# F3-Quad-Brushed-SIDE-USB.net
KiCad netlist of a schematic drawn in EAGLE
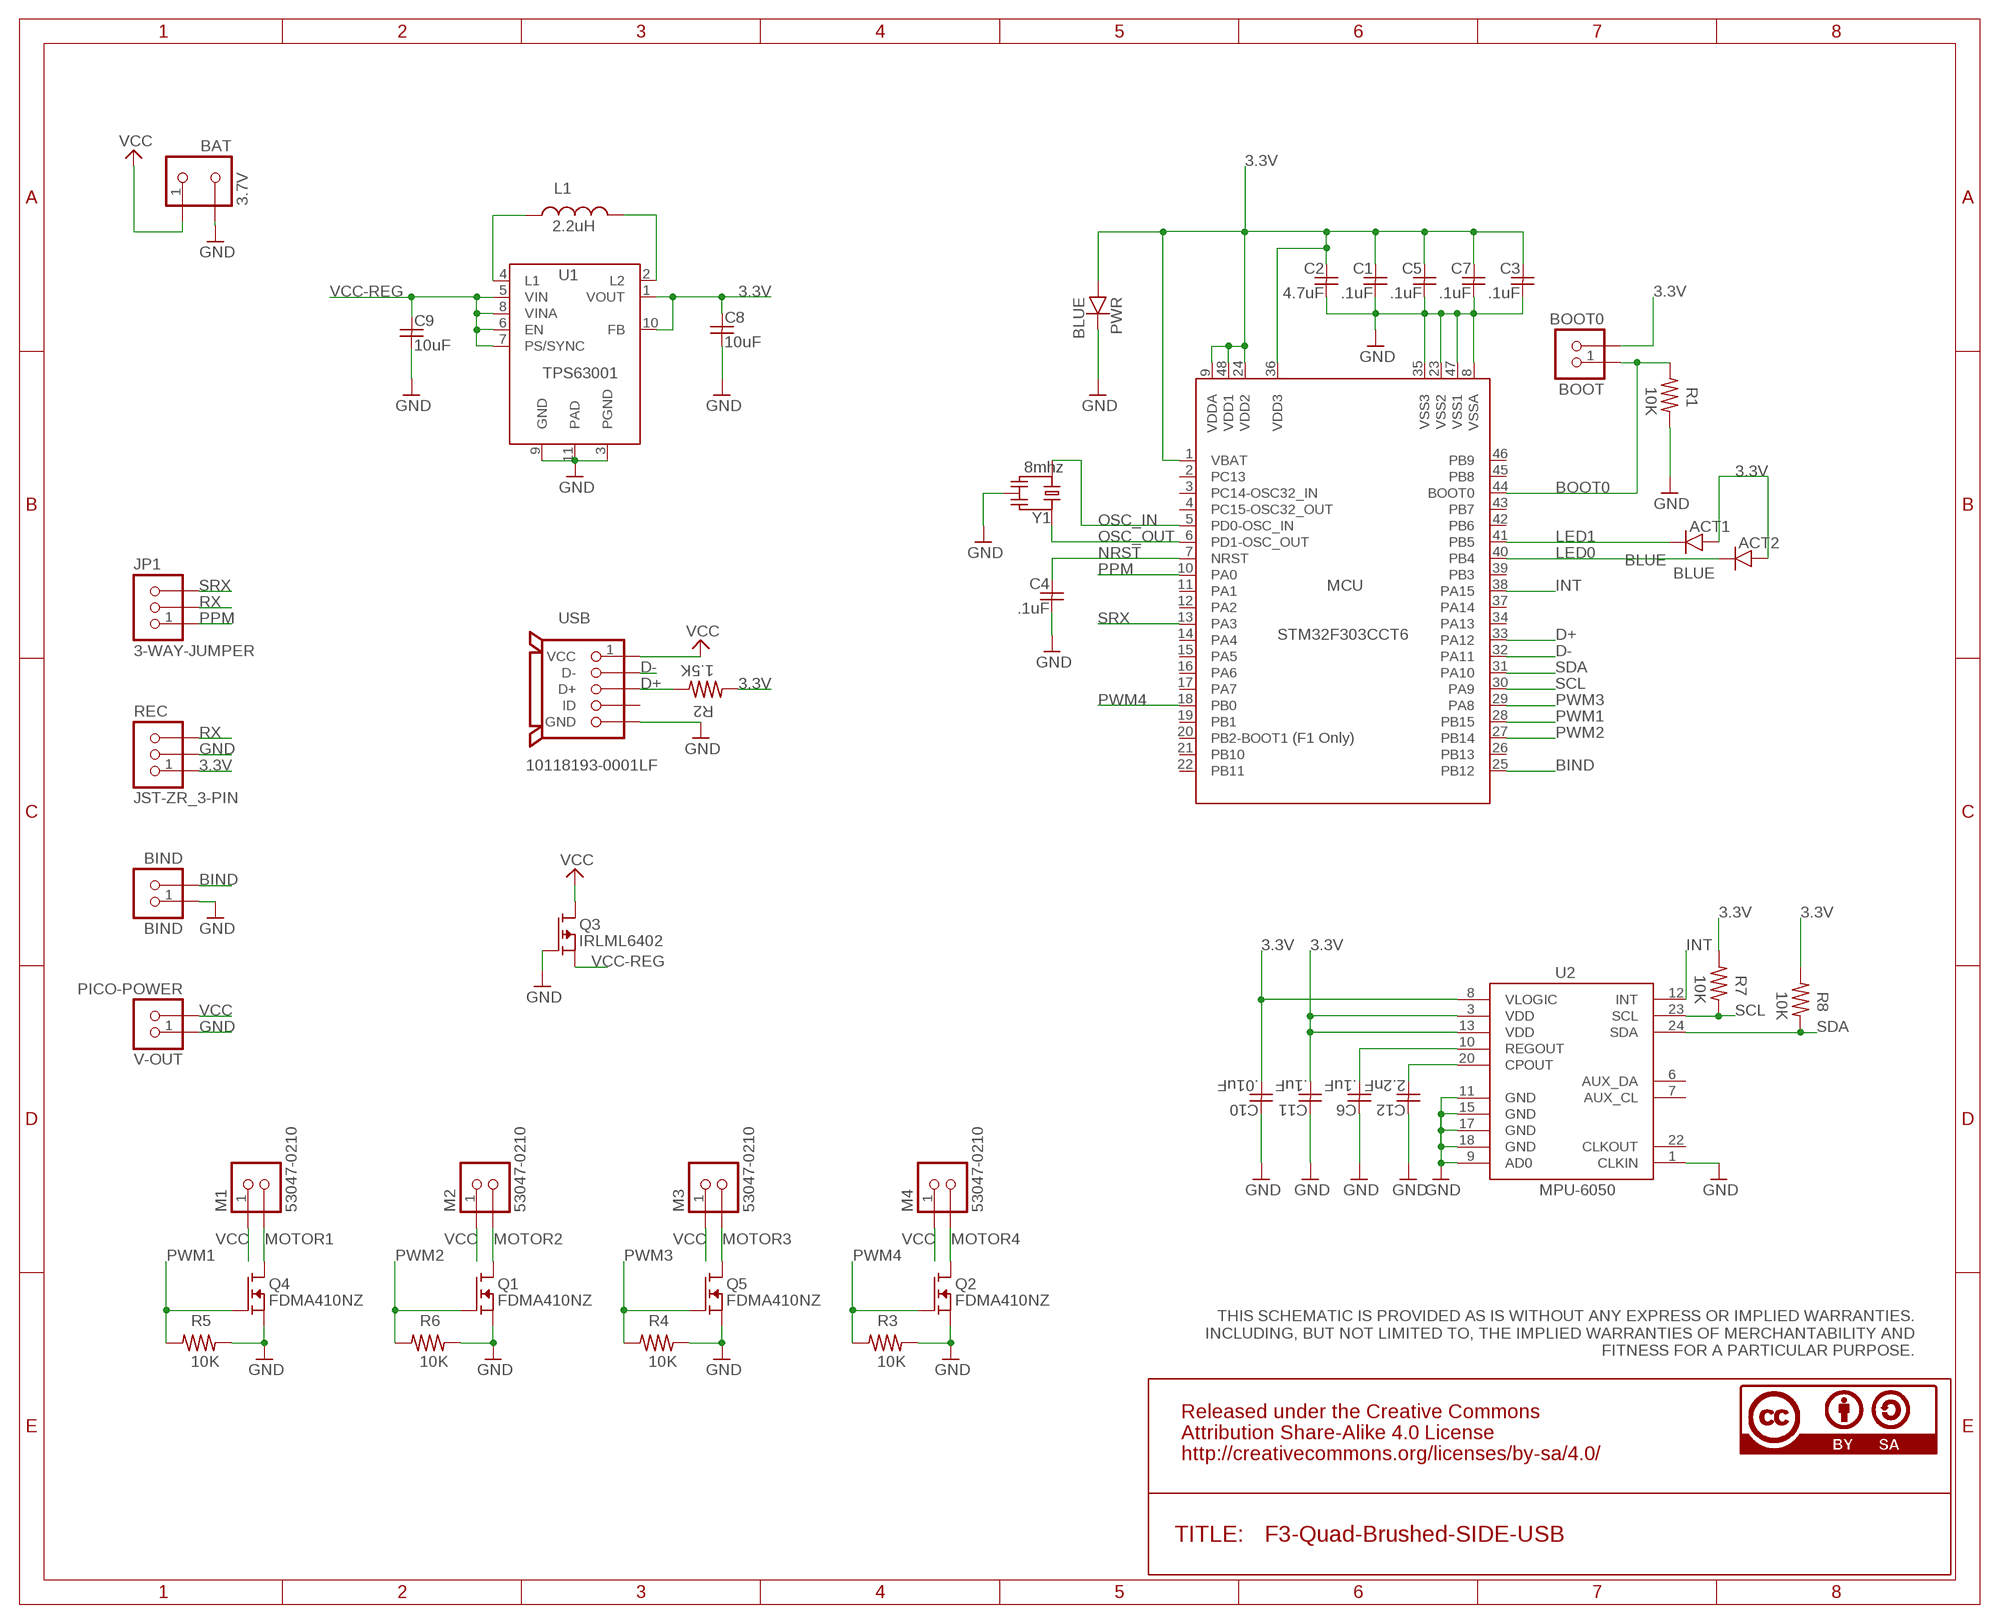
[diagram p0: schematic, sheet 1]

(export (version "E")
  (design (tool "Eeschema 10.0.6"))
  (components
    (comp (ref "ACT1")
      (value "BLUE")
      (footprint "eagle-import:SMD-CHIP-LED-0805")
      (fields (field (name "MF") "Kingbright") (field (name "MPN") "APHCM2012QBC/D-F01"))
      (libsource (lib "eagle-import") (part "SMD-CHIP-LED-0805"))
    )
    (comp (ref "ACT2")
      (value "BLUE")
      (footprint "eagle-import:SMD-CHIP-LED-0805")
      (fields (field (name "MF") "Kingbright") (field (name "MPN") "APHCM2012QBC/D-F01"))
      (libsource (lib "eagle-import") (part "SMD-CHIP-LED-0805"))
    )
    (comp (ref "BAT")
      (value "3.7V")
      (footprint "eagle-import:S2B-PH-K-S")
      (fields (field (name "MF") "JST") (field (name "MPN") "S2B-PH-K-S"))
      (libsource (lib "eagle-import") (part "JST-PH-BAT"))
    )
    (comp (ref "BIND")
      (value "BIND")
      (footprint "eagle-import:B3U-1000P(M)")
      (fields (field (name "MF") "Omron") (field (name "MPN") "B3U-1000P"))
      (libsource (lib "eagle-import") (part "TACTILE-SWITCH"))
    )
    (comp (ref "BOOT")
      (value "BOOT0")
      (footprint "eagle-import:B3U-1000P(M)")
      (fields (field (name "MF") "Omron") (field (name "MPN") "B3U-1000P"))
      (libsource (lib "eagle-import") (part "TACTILE-SWITCH"))
    )
    (comp (ref "C1")
      (value ".1uF")
      (footprint "eagle-import:MUR-CAP-0603")
      (fields (field (name "MF") "Murata") (field (name "MPN") "GRM188R71C104KA01D"))
      (libsource (lib "eagle-import") (part "CAPACITOR.1UF"))
    )
    (comp (ref "C2")
      (value "4.7uF")
      (footprint "eagle-import:MUR-CAP-0603")
      (fields (field (name "MF") "Murata") (field (name "MPN") "GRJ188C70J475KE11D"))
      (libsource (lib "eagle-import") (part "CAPACITOR4.7UF"))
    )
    (comp (ref "C3")
      (value ".1uF")
      (footprint "eagle-import:MUR-CAP-0603")
      (fields (field (name "MF") "Murata") (field (name "MPN") "GRM188R71C104KA01D"))
      (libsource (lib "eagle-import") (part "CAPACITOR.1UF"))
    )
    (comp (ref "C4")
      (value ".1uF")
      (footprint "eagle-import:MUR-CAP-0603")
      (fields (field (name "MF") "Murata") (field (name "MPN") "GRM188R71C104KA01D"))
      (libsource (lib "eagle-import") (part "CAPACITOR.1UF"))
    )
    (comp (ref "C5")
      (value ".1uF")
      (footprint "eagle-import:MUR-CAP-0603")
      (fields (field (name "MF") "Murata") (field (name "MPN") "GRM188R71C104KA01D"))
      (libsource (lib "eagle-import") (part "CAPACITOR.1UF"))
    )
    (comp (ref "C6")
      (value ".1uF")
      (footprint "eagle-import:MUR-CAP-0603")
      (fields (field (name "MF") "Murata") (field (name "MPN") "GRM188R71C104KA01D"))
      (libsource (lib "eagle-import") (part "CAPACITOR.1UF"))
    )
    (comp (ref "C7")
      (value ".1uF")
      (footprint "eagle-import:MUR-CAP-0603")
      (fields (field (name "MF") "Murata") (field (name "MPN") "GRM188R71C104KA01D"))
      (libsource (lib "eagle-import") (part "CAPACITOR.1UF"))
    )
    (comp (ref "C8")
      (value "10uF")
      (footprint "eagle-import:YUDEN-CAP-0805")
      (fields (field (name "MF") "Taiyo Yuden") (field (name "MPN") "JMK212AB7106KG-T"))
      (libsource (lib "eagle-import") (part "CAPACITOR10UF"))
    )
    (comp (ref "C9")
      (value "10uF")
      (footprint "eagle-import:YUDEN-CAP-0805")
      (fields (field (name "MF") "Taiyo Yuden") (field (name "MPN") "JMK212AB7106KG-T"))
      (libsource (lib "eagle-import") (part "CAPACITOR10UF"))
    )
    (comp (ref "C10")
      (value ".01uF")
      (footprint "eagle-import:MUR-CAP-0603")
      (fields (field (name "MF") "Murata") (field (name "MPN") "GRM188R71C103KA01D"))
      (libsource (lib "eagle-import") (part "CAPACITOR.01UF"))
    )
    (comp (ref "C11")
      (value ".1uF")
      (footprint "eagle-import:MUR-CAP-0603")
      (fields (field (name "MF") "Murata") (field (name "MPN") "GRM188R71C104KA01D"))
      (libsource (lib "eagle-import") (part "CAPACITOR.1UF"))
    )
    (comp (ref "C12")
      (value "2.2nF")
      (footprint "eagle-import:MUR-CAP-0603")
      (fields (field (name "MF") "Murata") (field (name "MPN") "GRM188R71C222KA01D"))
      (libsource (lib "eagle-import") (part "CAPACITOR2.2NF"))
    )
    (comp (ref "JP1")
      (value "3-WAY-JUMPER")
      (footprint "eagle-import:3-WAY-JUMPER")
      (libsource (lib "eagle-import") (part "3-WAY-JUMPER"))
    )
    (comp (ref "L1")
      (value "2.2uH")
      (footprint "eagle-import:NR301X")
      (fields (field (name "MF") "Taiyo Yuden") (field (name "MPN") "NR3015T2R2M"))
      (libsource (lib "eagle-import") (part "NR301X"))
    )
    (comp (ref "M1")
      (value "53047-0210")
      (footprint "eagle-import:PICO-53047-02")
      (fields (field (name "MF") "MOLEX"))
      (libsource (lib "eagle-import") (part "PICO-1.25-MOTOR"))
    )
    (comp (ref "M2")
      (value "53047-0210")
      (footprint "eagle-import:PICO-53047-02")
      (fields (field (name "MF") "MOLEX"))
      (libsource (lib "eagle-import") (part "PICO-1.25-MOTOR"))
    )
    (comp (ref "M3")
      (value "53047-0210")
      (footprint "eagle-import:PICO-53047-02")
      (fields (field (name "MF") "MOLEX"))
      (libsource (lib "eagle-import") (part "PICO-1.25-MOTOR"))
    )
    (comp (ref "M4")
      (value "53047-0210")
      (footprint "eagle-import:PICO-53047-02")
      (fields (field (name "MF") "MOLEX"))
      (libsource (lib "eagle-import") (part "PICO-1.25-MOTOR"))
    )
    (comp (ref "MCU")
      (value "STM32F303CCT6")
      (footprint "eagle-import:LQFP48-7X7")
      (fields (field (name "MF") "ST"))
      (libsource (lib "eagle-import") (part "STM32FX03-F3"))
    )
    (comp (ref "PWR")
      (value "BLUE")
      (footprint "eagle-import:SMD-CHIP-LED-0805")
      (fields (field (name "MF") "Kingbright") (field (name "MPN") "APHCM2012QBC/D-F01"))
      (libsource (lib "eagle-import") (part "SMD-CHIP-LED-0805"))
    )
    (comp (ref "Q1")
      (value "FDMA410NZ")
      (footprint "eagle-import:MICROFET-2X2")
      (fields (field (name "MF") "Fairchild"))
      (libsource (lib "eagle-import") (part "FDMA410NZ"))
    )
    (comp (ref "Q2")
      (value "FDMA410NZ")
      (footprint "eagle-import:MICROFET-2X2")
      (fields (field (name "MF") "Fairchild"))
      (libsource (lib "eagle-import") (part "FDMA410NZ"))
    )
    (comp (ref "Q3")
      (value "IRLML6402")
      (footprint "eagle-import:SOT-23")
      (fields (field (name "MF") "IR"))
      (libsource (lib "eagle-import") (part "MOSFET-P"))
    )
    (comp (ref "Q4")
      (value "FDMA410NZ")
      (footprint "eagle-import:MICROFET-2X2")
      (fields (field (name "MF") "Fairchild"))
      (libsource (lib "eagle-import") (part "FDMA410NZ"))
    )
    (comp (ref "Q5")
      (value "FDMA410NZ")
      (footprint "eagle-import:MICROFET-2X2")
      (fields (field (name "MF") "Fairchild"))
      (libsource (lib "eagle-import") (part "FDMA410NZ"))
    )
    (comp (ref "R1")
      (value "10K")
      (footprint "eagle-import:VISH-RES-0603")
      (fields (field (name "MF") "Vishay") (field (name "MPN") "CRCW060310K0FKEAHP"))
      (libsource (lib "eagle-import") (part "RESISTOR10K"))
    )
    (comp (ref "R2")
      (value "1.5K")
      (footprint "eagle-import:VISH-RES-0603")
      (fields (field (name "MF") "Vishay") (field (name "MPN") "CRCW06031K50FKEAHP"))
      (libsource (lib "eagle-import") (part "RESISTOR1.5K"))
    )
    (comp (ref "R3")
      (value "10K")
      (footprint "eagle-import:VISH-RES-0603")
      (fields (field (name "MF") "Vishay") (field (name "MPN") "CRCW060310K0FKEAHP"))
      (libsource (lib "eagle-import") (part "RESISTOR10K"))
    )
    (comp (ref "R4")
      (value "10K")
      (footprint "eagle-import:VISH-RES-0603")
      (fields (field (name "MF") "Vishay") (field (name "MPN") "CRCW060310K0FKEAHP"))
      (libsource (lib "eagle-import") (part "RESISTOR10K"))
    )
    (comp (ref "R5")
      (value "10K")
      (footprint "eagle-import:VISH-RES-0603")
      (fields (field (name "MF") "Vishay") (field (name "MPN") "CRCW060310K0FKEAHP"))
      (libsource (lib "eagle-import") (part "RESISTOR10K"))
    )
    (comp (ref "R6")
      (value "10K")
      (footprint "eagle-import:VISH-RES-0603")
      (fields (field (name "MF") "Vishay") (field (name "MPN") "CRCW060310K0FKEAHP"))
      (libsource (lib "eagle-import") (part "RESISTOR10K"))
    )
    (comp (ref "R7")
      (value "10K")
      (footprint "eagle-import:VISH-RES-0603")
      (fields (field (name "MF") "Vishay") (field (name "MPN") "CRCW060310K0FKEAHP"))
      (libsource (lib "eagle-import") (part "RESISTOR10K"))
    )
    (comp (ref "R8")
      (value "10K")
      (footprint "eagle-import:VISH-RES-0603")
      (fields (field (name "MF") "Vishay") (field (name "MPN") "CRCW060310K0FKEAHP"))
      (libsource (lib "eagle-import") (part "RESISTOR10K"))
    )
    (comp (ref "REC")
      (value "JST-ZR_3-PIN")
      (footprint "eagle-import:S3B-ZR")
      (fields (field (name "MF") "JST") (field (name "MPN") "S3B-ZR"))
      (libsource (lib "eagle-import") (part "JST-ZR_3-PIN"))
    )
    (comp (ref "U1")
      (value "TPS63001")
      (footprint "eagle-import:VSON-N10")
      (fields (field (name "MF") "TI") (field (name "MPN") "TPS63001DRCR"))
      (libsource (lib "eagle-import") (part "TPS630XX-TPS63001"))
    )
    (comp (ref "U2")
      (value "MPU-6050")
      (footprint "eagle-import:QFN24-4X4")
      (fields (field (name "MF") "Invensense"))
      (libsource (lib "eagle-import") (part "MPU-6050"))
    )
    (comp (ref "USB")
      (value "10118193-0001LF")
      (footprint "eagle-import:10118193-0001LF")
      (fields (field (name "MF") "FCI"))
      (libsource (lib "eagle-import") (part "USB-MICRO-B-FCI"))
    )
    (comp (ref "V-OUT")
      (value "PICO-POWER")
      (footprint "eagle-import:PICO_1.25_.5MM")
      (fields (field (name "MF") "Molex") (field (name "MPN") "53047-0210"))
      (libsource (lib "eagle-import") (part "PICO-POWER"))
    )
    (comp (ref "Y1")
      (value "8mhz")
      (footprint "eagle-import:RESONATOR_8")
      (fields (field (name "MF") "Murata") (field (name "MPN") "CSTCE8M00G55-R0"))
      (libsource (lib "eagle-import") (part "RESONATOR8MHZ"))
    )
  )
  (nets
    (net (code "1") (name "/3.3V") (class "Default")
      (node (ref "ACT1") (pin "A") (pinfunction "A_A") (pintype "passive"))
      (node (ref "ACT2") (pin "A") (pinfunction "A_A") (pintype "passive"))
      (node (ref "BOOT") (pin "2") (pinfunction "2_2") (pintype "passive"))
      (node (ref "C1") (pin "1") (pinfunction "1_1") (pintype "passive"))
      (node (ref "C10") (pin "2") (pinfunction "2_2") (pintype "passive"))
      (node (ref "C11") (pin "2") (pinfunction "2_2") (pintype "passive"))
      (node (ref "C2") (pin "1") (pinfunction "1_1") (pintype "passive"))
      (node (ref "C3") (pin "1") (pinfunction "1_1") (pintype "passive"))
      (node (ref "C5") (pin "1") (pinfunction "1_1") (pintype "passive"))
      (node (ref "C7") (pin "1") (pinfunction "1_1") (pintype "passive"))
      (node (ref "C8") (pin "1") (pinfunction "1_1") (pintype "passive"))
      (node (ref "MCU") (pin "1") (pinfunction "VBAT_1") (pintype "bidirectional"))
      (node (ref "MCU") (pin "24") (pinfunction "VDD2_24") (pintype "bidirectional"))
      (node (ref "MCU") (pin "36") (pinfunction "VDD3_36") (pintype "bidirectional"))
      (node (ref "MCU") (pin "48") (pinfunction "VDD1_48") (pintype "bidirectional"))
      (node (ref "MCU") (pin "9") (pinfunction "VDDA_9") (pintype "bidirectional"))
      (node (ref "PWR") (pin "A") (pinfunction "A_A") (pintype "passive"))
      (node (ref "R2") (pin "2") (pinfunction "2_2") (pintype "passive"))
      (node (ref "R7") (pin "2") (pinfunction "2_2") (pintype "passive"))
      (node (ref "R8") (pin "2") (pinfunction "2_2") (pintype "passive"))
      (node (ref "REC") (pin "1") (pinfunction "1_1") (pintype "bidirectional"))
      (node (ref "U1") (pin "1") (pinfunction "VOUT_1") (pintype "bidirectional"))
      (node (ref "U1") (pin "10") (pinfunction "FB_10") (pintype "bidirectional"))
      (node (ref "U2") (pin "13") (pinfunction "VDD_13") (pintype "bidirectional"))
      (node (ref "U2") (pin "3") (pinfunction "VDD_3") (pintype "bidirectional"))
      (node (ref "U2") (pin "8") (pinfunction "VLOGIC_8") (pintype "bidirectional"))
    )
    (net (code "2") (name "/BIND") (class "Default")
      (node (ref "BIND") (pin "2") (pinfunction "2_2") (pintype "passive"))
      (node (ref "MCU") (pin "25") (pinfunction "PB12_25") (pintype "bidirectional"))
    )
    (net (code "3") (name "/BOOT0") (class "Default")
      (node (ref "BOOT") (pin "1") (pinfunction "1_1") (pintype "passive"))
      (node (ref "MCU") (pin "44") (pinfunction "BOOT0_44") (pintype "bidirectional"))
      (node (ref "R1") (pin "2") (pinfunction "2_2") (pintype "passive"))
    )
    (net (code "4") (name "/D+") (class "Default")
      (node (ref "MCU") (pin "33") (pinfunction "PA12_33") (pintype "bidirectional"))
      (node (ref "R2") (pin "1") (pinfunction "1_1") (pintype "passive"))
      (node (ref "USB") (pin "3") (pinfunction "D+_3") (pintype "passive"))
    )
    (net (code "5") (name "/D-") (class "Default")
      (node (ref "MCU") (pin "32") (pinfunction "PA11_32") (pintype "bidirectional"))
      (node (ref "USB") (pin "2") (pinfunction "D-_2") (pintype "passive"))
    )
    (net (code "6") (name "/INT") (class "Default")
      (node (ref "MCU") (pin "38") (pinfunction "PA15_38") (pintype "bidirectional"))
      (node (ref "U2") (pin "12") (pinfunction "INT_12") (pintype "bidirectional"))
    )
    (net (code "7") (name "/LED0") (class "Default")
      (node (ref "ACT2") (pin "C") (pinfunction "C_C") (pintype "passive"))
      (node (ref "MCU") (pin "40") (pinfunction "PB4_40") (pintype "bidirectional"))
    )
    (net (code "8") (name "/LED1") (class "Default")
      (node (ref "ACT1") (pin "C") (pinfunction "C_C") (pintype "passive"))
      (node (ref "MCU") (pin "41") (pinfunction "PB5_41") (pintype "bidirectional"))
    )
    (net (code "9") (name "/MOTOR1") (class "Default")
      (node (ref "M1") (pin "2") (pinfunction "2_2") (pintype "passive"))
      (node (ref "Q4") (pin "D") (pinfunction "D_D") (pintype "bidirectional"))
      (node (ref "Q4") (pin "D1") (pinfunction "D_D1") (pintype "bidirectional"))
      (node (ref "Q4") (pin "D2") (pinfunction "D_D2") (pintype "bidirectional"))
      (node (ref "Q4") (pin "D3") (pinfunction "D_D3") (pintype "bidirectional"))
      (node (ref "Q4") (pin "D4") (pinfunction "D_D4") (pintype "bidirectional"))
    )
    (net (code "10") (name "/MOTOR2") (class "Default")
      (node (ref "M2") (pin "2") (pinfunction "2_2") (pintype "passive"))
      (node (ref "Q1") (pin "D") (pinfunction "D_D") (pintype "bidirectional"))
      (node (ref "Q1") (pin "D1") (pinfunction "D_D1") (pintype "bidirectional"))
      (node (ref "Q1") (pin "D2") (pinfunction "D_D2") (pintype "bidirectional"))
      (node (ref "Q1") (pin "D3") (pinfunction "D_D3") (pintype "bidirectional"))
      (node (ref "Q1") (pin "D4") (pinfunction "D_D4") (pintype "bidirectional"))
    )
    (net (code "11") (name "/MOTOR3") (class "Default")
      (node (ref "M3") (pin "2") (pinfunction "2_2") (pintype "passive"))
      (node (ref "Q5") (pin "D") (pinfunction "D_D") (pintype "bidirectional"))
      (node (ref "Q5") (pin "D1") (pinfunction "D_D1") (pintype "bidirectional"))
      (node (ref "Q5") (pin "D2") (pinfunction "D_D2") (pintype "bidirectional"))
      (node (ref "Q5") (pin "D3") (pinfunction "D_D3") (pintype "bidirectional"))
      (node (ref "Q5") (pin "D4") (pinfunction "D_D4") (pintype "bidirectional"))
    )
    (net (code "12") (name "/MOTOR4") (class "Default")
      (node (ref "M4") (pin "2") (pinfunction "2_2") (pintype "passive"))
      (node (ref "Q2") (pin "D") (pinfunction "D_D") (pintype "bidirectional"))
      (node (ref "Q2") (pin "D1") (pinfunction "D_D1") (pintype "bidirectional"))
      (node (ref "Q2") (pin "D2") (pinfunction "D_D2") (pintype "bidirectional"))
      (node (ref "Q2") (pin "D3") (pinfunction "D_D3") (pintype "bidirectional"))
      (node (ref "Q2") (pin "D4") (pinfunction "D_D4") (pintype "bidirectional"))
    )
    (net (code "13") (name "/NRST") (class "Default")
      (node (ref "C4") (pin "1") (pinfunction "1_1") (pintype "passive"))
      (node (ref "MCU") (pin "7") (pinfunction "NRST_7") (pintype "bidirectional"))
    )
    (net (code "14") (name "/OSC_IN") (class "Default")
      (node (ref "MCU") (pin "5") (pinfunction "PD0-OSC_IN_5") (pintype "bidirectional"))
      (node (ref "Y1") (pin "3") (pinfunction "3_3") (pintype "passive"))
    )
    (net (code "15") (name "/OSC_OUT") (class "Default")
      (node (ref "MCU") (pin "6") (pinfunction "PD1-OSC_OUT_6") (pintype "bidirectional"))
      (node (ref "Y1") (pin "1") (pinfunction "1_1") (pintype "passive"))
    )
    (net (code "16") (name "/PPM") (class "Default")
      (node (ref "JP1") (pin "1") (pinfunction "1_1") (pintype "bidirectional"))
      (node (ref "MCU") (pin "10") (pinfunction "PA0_10") (pintype "bidirectional"))
    )
    (net (code "17") (name "/PWM1") (class "Default")
      (node (ref "MCU") (pin "28") (pinfunction "PB15_28") (pintype "bidirectional"))
      (node (ref "Q4") (pin "G") (pinfunction "G_G") (pintype "bidirectional"))
      (node (ref "R5") (pin "2") (pinfunction "2_2") (pintype "passive"))
    )
    (net (code "18") (name "/PWM2") (class "Default")
      (node (ref "MCU") (pin "27") (pinfunction "PB14_27") (pintype "bidirectional"))
      (node (ref "Q1") (pin "G") (pinfunction "G_G") (pintype "bidirectional"))
      (node (ref "R6") (pin "2") (pinfunction "2_2") (pintype "passive"))
    )
    (net (code "19") (name "/PWM3") (class "Default")
      (node (ref "MCU") (pin "29") (pinfunction "PA8_29") (pintype "bidirectional"))
      (node (ref "Q5") (pin "G") (pinfunction "G_G") (pintype "bidirectional"))
      (node (ref "R4") (pin "2") (pinfunction "2_2") (pintype "passive"))
    )
    (net (code "20") (name "/PWM4") (class "Default")
      (node (ref "MCU") (pin "18") (pinfunction "PB0_18") (pintype "bidirectional"))
      (node (ref "Q2") (pin "G") (pinfunction "G_G") (pintype "bidirectional"))
      (node (ref "R3") (pin "2") (pinfunction "2_2") (pintype "passive"))
    )
    (net (code "21") (name "/RX") (class "Default")
      (node (ref "JP1") (pin "2") (pinfunction "2_2") (pintype "bidirectional"))
      (node (ref "REC") (pin "3") (pinfunction "3_3") (pintype "bidirectional"))
    )
    (net (code "22") (name "/SCL") (class "Default")
      (node (ref "MCU") (pin "30") (pinfunction "PA9_30") (pintype "bidirectional"))
      (node (ref "R7") (pin "1") (pinfunction "1_1") (pintype "passive"))
      (node (ref "U2") (pin "23") (pinfunction "SCL_23") (pintype "bidirectional"))
    )
    (net (code "23") (name "/SDA") (class "Default")
      (node (ref "MCU") (pin "31") (pinfunction "PA10_31") (pintype "bidirectional"))
      (node (ref "R8") (pin "1") (pinfunction "1_1") (pintype "passive"))
      (node (ref "U2") (pin "24") (pinfunction "SDA_24") (pintype "bidirectional"))
    )
    (net (code "24") (name "/SRX") (class "Default")
      (node (ref "JP1") (pin "3") (pinfunction "3_3") (pintype "bidirectional"))
      (node (ref "MCU") (pin "13") (pinfunction "PA3_13") (pintype "bidirectional"))
    )
    (net (code "25") (name "/VCC-REG") (class "Default")
      (node (ref "C9") (pin "1") (pinfunction "1_1") (pintype "passive"))
      (node (ref "Q3") (pin "2") (pinfunction "S_2") (pintype "bidirectional"))
      (node (ref "U1") (pin "5") (pinfunction "VIN_5") (pintype "bidirectional"))
      (node (ref "U1") (pin "6") (pinfunction "EN_6") (pintype "bidirectional"))
      (node (ref "U1") (pin "7") (pinfunction "PS/SYNC_7") (pintype "bidirectional"))
      (node (ref "U1") (pin "8") (pinfunction "VINA_8") (pintype "bidirectional"))
    )
    (net (code "26") (name "GND") (class "Default")
      (node (ref "BAT") (pin "2") (pinfunction "2_2") (pintype "bidirectional"))
      (node (ref "BIND") (pin "1") (pinfunction "1_1") (pintype "passive"))
      (node (ref "C1") (pin "2") (pinfunction "2_2") (pintype "passive"))
      (node (ref "C10") (pin "1") (pinfunction "1_1") (pintype "passive"))
      (node (ref "C11") (pin "1") (pinfunction "1_1") (pintype "passive"))
      (node (ref "C12") (pin "1") (pinfunction "1_1") (pintype "passive"))
      (node (ref "C2") (pin "2") (pinfunction "2_2") (pintype "passive"))
      (node (ref "C3") (pin "2") (pinfunction "2_2") (pintype "passive"))
      (node (ref "C4") (pin "2") (pinfunction "2_2") (pintype "passive"))
      (node (ref "C5") (pin "2") (pinfunction "2_2") (pintype "passive"))
      (node (ref "C6") (pin "1") (pinfunction "1_1") (pintype "passive"))
      (node (ref "C7") (pin "2") (pinfunction "2_2") (pintype "passive"))
      (node (ref "C8") (pin "2") (pinfunction "2_2") (pintype "passive"))
      (node (ref "C9") (pin "2") (pinfunction "2_2") (pintype "passive"))
      (node (ref "MCU") (pin "23") (pinfunction "VSS2_23") (pintype "bidirectional"))
      (node (ref "MCU") (pin "35") (pinfunction "VSS3_35") (pintype "bidirectional"))
      (node (ref "MCU") (pin "47") (pinfunction "VSS1_47") (pintype "bidirectional"))
      (node (ref "MCU") (pin "8") (pinfunction "VSSA_8") (pintype "bidirectional"))
      (node (ref "PWR") (pin "C") (pinfunction "C_C") (pintype "passive"))
      (node (ref "Q1") (pin "S") (pinfunction "S_S") (pintype "bidirectional"))
      (node (ref "Q1") (pin "S1") (pinfunction "S_S1") (pintype "bidirectional"))
      (node (ref "Q2") (pin "S") (pinfunction "S_S") (pintype "bidirectional"))
      (node (ref "Q2") (pin "S1") (pinfunction "S_S1") (pintype "bidirectional"))
      (node (ref "Q3") (pin "1") (pinfunction "G_1") (pintype "bidirectional"))
      (node (ref "Q4") (pin "S") (pinfunction "S_S") (pintype "bidirectional"))
      (node (ref "Q4") (pin "S1") (pinfunction "S_S1") (pintype "bidirectional"))
      (node (ref "Q5") (pin "S") (pinfunction "S_S") (pintype "bidirectional"))
      (node (ref "Q5") (pin "S1") (pinfunction "S_S1") (pintype "bidirectional"))
      (node (ref "R1") (pin "1") (pinfunction "1_1") (pintype "passive"))
      (node (ref "R3") (pin "1") (pinfunction "1_1") (pintype "passive"))
      (node (ref "R4") (pin "1") (pinfunction "1_1") (pintype "passive"))
      (node (ref "R5") (pin "1") (pinfunction "1_1") (pintype "passive"))
      (node (ref "R6") (pin "1") (pinfunction "1_1") (pintype "passive"))
      (node (ref "REC") (pin "2") (pinfunction "2_2") (pintype "bidirectional"))
      (node (ref "U1") (pin "11") (pinfunction "PAD_11") (pintype "bidirectional"))
      (node (ref "U1") (pin "3") (pinfunction "PGND_3") (pintype "bidirectional"))
      (node (ref "U1") (pin "9") (pinfunction "GND_9") (pintype "bidirectional"))
      (node (ref "U2") (pin "1") (pinfunction "CLKIN_1") (pintype "bidirectional"))
      (node (ref "U2") (pin "11") (pinfunction "GND_11") (pintype "bidirectional"))
      (node (ref "U2") (pin "15") (pinfunction "GND_15") (pintype "bidirectional"))
      (node (ref "U2") (pin "17") (pinfunction "GND_17") (pintype "bidirectional"))
      (node (ref "U2") (pin "18") (pinfunction "GND_18") (pintype "bidirectional"))
      (node (ref "U2") (pin "9") (pinfunction "AD0_9") (pintype "bidirectional"))
      (node (ref "USB") (pin "5") (pinfunction "GND_5") (pintype "passive"))
      (node (ref "USB") (pin "GND") (pinfunction "GND_GND") (pintype "passive"))
      (node (ref "USB") (pin "GND2") (pinfunction "GND_GND2") (pintype "passive"))
      (node (ref "USB") (pin "HOLE1") (pinfunction "GND_HOLE1") (pintype "passive"))
      (node (ref "USB") (pin "HOLE2") (pinfunction "GND_HOLE2") (pintype "passive"))
      (node (ref "V-OUT") (pin "1") (pinfunction "1_1") (pintype "passive"))
      (node (ref "Y1") (pin "2") (pinfunction "2_2") (pintype "passive"))
    )
    (net (code "27") (name "Net-(U1-L1)") (class "Default")
      (node (ref "L1") (pin "1") (pinfunction "1_1") (pintype "passive"))
      (node (ref "U1") (pin "4") (pinfunction "L1_4") (pintype "bidirectional"))
    )
    (net (code "28") (name "Net-(U1-L2)") (class "Default")
      (node (ref "L1") (pin "2") (pinfunction "2_2") (pintype "passive"))
      (node (ref "U1") (pin "2") (pinfunction "L2_2") (pintype "bidirectional"))
    )
    (net (code "29") (name "Net-(U2-CPOUT)") (class "Default")
      (node (ref "C12") (pin "2") (pinfunction "2_2") (pintype "passive"))
      (node (ref "U2") (pin "20") (pinfunction "CPOUT_20") (pintype "bidirectional"))
    )
    (net (code "30") (name "Net-(U2-REGOUT)") (class "Default")
      (node (ref "C6") (pin "2") (pinfunction "2_2") (pintype "passive"))
      (node (ref "U2") (pin "10") (pinfunction "REGOUT_10") (pintype "bidirectional"))
    )
    (net (code "31") (name "VCC") (class "Default")
      (node (ref "BAT") (pin "1") (pinfunction "1_1") (pintype "bidirectional"))
      (node (ref "M1") (pin "1") (pinfunction "1_1") (pintype "passive"))
      (node (ref "M2") (pin "1") (pinfunction "1_1") (pintype "passive"))
      (node (ref "M3") (pin "1") (pinfunction "1_1") (pintype "passive"))
      (node (ref "M4") (pin "1") (pinfunction "1_1") (pintype "passive"))
      (node (ref "Q3") (pin "3") (pinfunction "D_3") (pintype "bidirectional"))
      (node (ref "USB") (pin "1") (pinfunction "VCC_1") (pintype "passive"))
      (node (ref "V-OUT") (pin "2") (pinfunction "2_2") (pintype "passive"))
    )
    (net (code "32") (name "unconnected-(MCU-PA1-Pad11)") (class "Default")
      (node (ref "MCU") (pin "11") (pinfunction "PA1_11") (pintype "bidirectional"))
    )
    (net (code "33") (name "unconnected-(MCU-PA2-Pad12)") (class "Default")
      (node (ref "MCU") (pin "12") (pinfunction "PA2_12") (pintype "bidirectional"))
    )
    (net (code "34") (name "unconnected-(MCU-PA4-Pad14)") (class "Default")
      (node (ref "MCU") (pin "14") (pinfunction "PA4_14") (pintype "bidirectional"))
    )
    (net (code "35") (name "unconnected-(MCU-PA5-Pad15)") (class "Default")
      (node (ref "MCU") (pin "15") (pinfunction "PA5_15") (pintype "bidirectional"))
    )
    (net (code "36") (name "unconnected-(MCU-PA6-Pad16)") (class "Default")
      (node (ref "MCU") (pin "16") (pinfunction "PA6_16") (pintype "bidirectional"))
    )
    (net (code "37") (name "unconnected-(MCU-PA7-Pad17)") (class "Default")
      (node (ref "MCU") (pin "17") (pinfunction "PA7_17") (pintype "bidirectional"))
    )
    (net (code "38") (name "unconnected-(MCU-PA13-Pad34)") (class "Default")
      (node (ref "MCU") (pin "34") (pinfunction "PA13_34") (pintype "bidirectional"))
    )
    (net (code "39") (name "unconnected-(MCU-PA14-Pad37)") (class "Default")
      (node (ref "MCU") (pin "37") (pinfunction "PA14_37") (pintype "bidirectional"))
    )
    (net (code "40") (name "unconnected-(MCU-PB1-Pad19)") (class "Default")
      (node (ref "MCU") (pin "19") (pinfunction "PB1_19") (pintype "bidirectional"))
    )
    (net (code "41") (name "unconnected-(MCU-PB2-BOOT1-Pad20)") (class "Default")
      (node (ref "MCU") (pin "20") (pinfunction "PB2-BOOT1_20") (pintype "bidirectional"))
    )
    (net (code "42") (name "unconnected-(MCU-PB3-Pad39)") (class "Default")
      (node (ref "MCU") (pin "39") (pinfunction "PB3_39") (pintype "bidirectional"))
    )
    (net (code "43") (name "unconnected-(MCU-PB6-Pad42)") (class "Default")
      (node (ref "MCU") (pin "42") (pinfunction "PB6_42") (pintype "bidirectional"))
    )
    (net (code "44") (name "unconnected-(MCU-PB7-Pad43)") (class "Default")
      (node (ref "MCU") (pin "43") (pinfunction "PB7_43") (pintype "bidirectional"))
    )
    (net (code "45") (name "unconnected-(MCU-PB8-Pad45)") (class "Default")
      (node (ref "MCU") (pin "45") (pinfunction "PB8_45") (pintype "bidirectional"))
    )
    (net (code "46") (name "unconnected-(MCU-PB9-Pad46)") (class "Default")
      (node (ref "MCU") (pin "46") (pinfunction "PB9_46") (pintype "bidirectional"))
    )
    (net (code "47") (name "unconnected-(MCU-PB10-Pad21)") (class "Default")
      (node (ref "MCU") (pin "21") (pinfunction "PB10_21") (pintype "bidirectional"))
    )
    (net (code "48") (name "unconnected-(MCU-PB11-Pad22)") (class "Default")
      (node (ref "MCU") (pin "22") (pinfunction "PB11_22") (pintype "bidirectional"))
    )
    (net (code "49") (name "unconnected-(MCU-PB13-Pad26)") (class "Default")
      (node (ref "MCU") (pin "26") (pinfunction "PB13_26") (pintype "bidirectional"))
    )
    (net (code "50") (name "unconnected-(MCU-PC13-Pad2)") (class "Default")
      (node (ref "MCU") (pin "2") (pinfunction "PC13_2") (pintype "bidirectional"))
    )
    (net (code "51") (name "unconnected-(MCU-PC14-OSC32_IN-Pad3)") (class "Default")
      (node (ref "MCU") (pin "3") (pinfunction "PC14-OSC32_IN_3") (pintype "bidirectional"))
    )
    (net (code "52") (name "unconnected-(MCU-PC15-OSC32_OUT-Pad4)") (class "Default")
      (node (ref "MCU") (pin "4") (pinfunction "PC15-OSC32_OUT_4") (pintype "bidirectional"))
    )
    (net (code "53") (name "unconnected-(U2-AUX_CL-Pad7)") (class "Default")
      (node (ref "U2") (pin "7") (pinfunction "AUX_CL_7") (pintype "bidirectional"))
    )
    (net (code "54") (name "unconnected-(U2-AUX_DA-Pad6)") (class "Default")
      (node (ref "U2") (pin "6") (pinfunction "AUX_DA_6") (pintype "bidirectional"))
    )
    (net (code "55") (name "unconnected-(U2-CLKOUT-Pad22)") (class "Default")
      (node (ref "U2") (pin "22") (pinfunction "CLKOUT_22") (pintype "bidirectional"))
    )
    (net (code "56") (name "unconnected-(USB-ID-Pad4)") (class "Default")
      (node (ref "USB") (pin "4") (pinfunction "ID_4") (pintype "passive"))
    )
  )
)
